# USB3A_CONN.net
KiCad netlist of a schematic drawn in Altium Designer
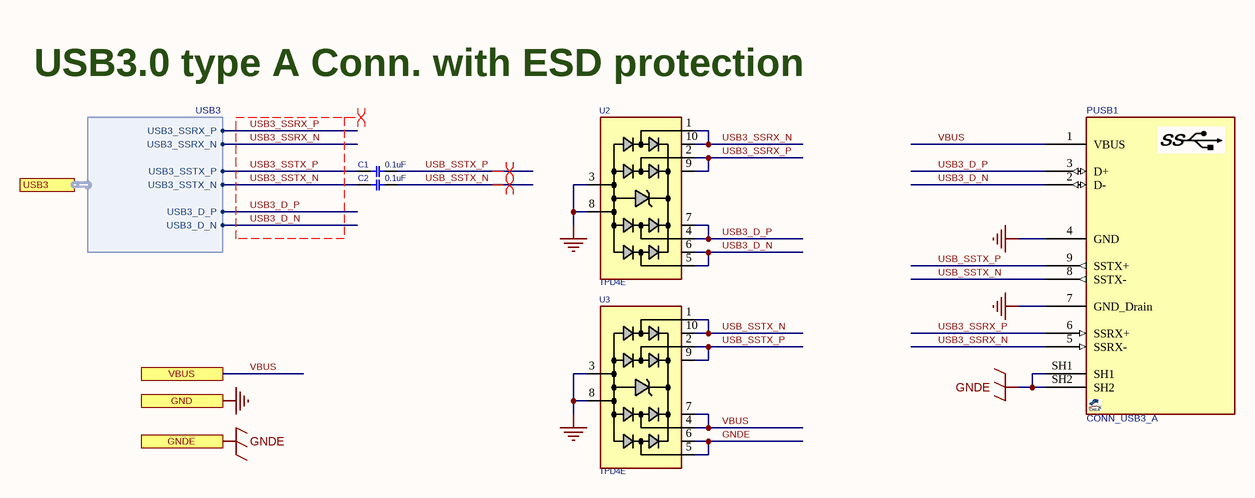
[diagram p0: USB3A_CONN.SchDoc]

(export (version "E")
  (design (tool "Eeschema 10.0.6"))
  (components
    (comp (ref "C1")
      (value "0.1uF")
      (footprint "C0201")
      (description "CAP, MLCC")
      (fields (field (name "MANF_P#") "GRM155R61E104") (field (name "MANF") "Murata"))
      (libsource (lib "passive_smd") (part "CAP_SMD_MLCC"))
    )
    (comp (ref "C2")
      (value "0.1uF")
      (footprint "C0201")
      (description "CAP, MLCC")
      (fields (field (name "MANF_P#") "GRM155R61E104") (field (name "MANF") "Murata"))
      (libsource (lib "passive_smd") (part "CAP_SMD_MLCC"))
    )
    (comp (ref "PUSB1")
      (value "CONN_USB3_A")
      (footprint "USB3_A_RA")
      (description "CONN, USB3, A type, R/A, THD")
      (fields (field (name "MANF_P#") "USB1075") (field (name "MANF") "GCT"))
      (libsource (lib "conn_usb") (part "CONN_USB3_A_USB1075"))
    )
    (comp (ref "U2")
      (value "TPD4E")
      (footprint "SON50_10_2510")
      (description "TVS, ESD PROTECT, 4CH,")
      (fields (field (name "MANF_P#") "TPD4E05U06DQA") (field (name "MANF") "Texas Instruments"))
      (libsource (lib "protect_tvs_esd_fuse") (part "TVS_X4_TPD4E05U06"))
    )
    (comp (ref "U3")
      (value "TPD4E")
      (footprint "SON50_10_2510")
      (description "TVS, ESD PROTECT, 4CH,")
      (fields (field (name "MANF_P#") "TPD4E05U06DQA") (field (name "MANF") "Texas Instruments"))
      (libsource (lib "protect_tvs_esd_fuse") (part "TVS_X4_TPD4E05U06"))
    )
  )
  (nets
    (net (code "2") (name "/USB3_D_N") (class "Default")
      (node (ref "PUSB1") (pin "2") (pinfunction "D-_2") (pintype "bidirectional"))
      (node (ref "U2") (pin "5") (pinfunction "5_5") (pintype "passive"))
      (node (ref "U2") (pin "6") (pinfunction "6_6") (pintype "passive"))
    )
    (net (code "3") (name "/USB3_D_P") (class "Default")
      (node (ref "PUSB1") (pin "3") (pinfunction "D+_3") (pintype "bidirectional"))
      (node (ref "U2") (pin "4") (pinfunction "4_4") (pintype "passive"))
      (node (ref "U2") (pin "7") (pinfunction "7_7") (pintype "passive"))
    )
    (net (code "4") (name "/USB3_SSRX_N") (class "Default")
      (node (ref "PUSB1") (pin "5") (pinfunction "SSRX-_5") (pintype "input"))
      (node (ref "U2") (pin "1") (pinfunction "1_1") (pintype "passive"))
      (node (ref "U2") (pin "10") (pinfunction "10_10") (pintype "passive"))
    )
    (net (code "5") (name "/USB3_SSRX_P") (class "Default")
      (node (ref "PUSB1") (pin "6") (pinfunction "SSRX+_6") (pintype "input"))
      (node (ref "U2") (pin "2") (pinfunction "2_2") (pintype "passive"))
      (node (ref "U2") (pin "9") (pinfunction "9_9") (pintype "passive"))
    )
    (net (code "6") (name "/USB3_SSTX_N") (class "Default")
      (node (ref "C2") (pin "1") (pinfunction "1_1") (pintype "passive"))
    )
    (net (code "7") (name "/USB3_SSTX_P") (class "Default")
      (node (ref "C1") (pin "1") (pinfunction "1_1") (pintype "passive"))
    )
    (net (code "8") (name "/USB_SSTX_N") (class "Default")
      (node (ref "C2") (pin "2") (pinfunction "2_2") (pintype "passive"))
      (node (ref "PUSB1") (pin "8") (pinfunction "SSTX-_8") (pintype "output"))
      (node (ref "U3") (pin "1") (pinfunction "1_1") (pintype "passive"))
      (node (ref "U3") (pin "10") (pinfunction "10_10") (pintype "passive"))
    )
    (net (code "9") (name "/USB_SSTX_P") (class "Default")
      (node (ref "C1") (pin "2") (pinfunction "2_2") (pintype "passive"))
      (node (ref "PUSB1") (pin "9") (pinfunction "SSTX+_9") (pintype "output"))
      (node (ref "U3") (pin "2") (pinfunction "2_2") (pintype "passive"))
      (node (ref "U3") (pin "9") (pinfunction "9_9") (pintype "passive"))
    )
    (net (code "10") (name "/VBUS") (class "Default")
      (node (ref "PUSB1") (pin "1") (pinfunction "VBUS_1") (pintype "power_in"))
      (node (ref "U3") (pin "4") (pinfunction "4_4") (pintype "passive"))
      (node (ref "U3") (pin "7") (pinfunction "7_7") (pintype "passive"))
    )
    (net (code "12") (name "GND") (class "Default")
      (node (ref "PUSB1") (pin "4") (pinfunction "GND_4") (pintype "power_in"))
      (node (ref "PUSB1") (pin "7") (pinfunction "GND_Drain_7") (pintype "power_in"))
      (node (ref "U2") (pin "3") (pinfunction "3_3") (pintype "passive"))
      (node (ref "U2") (pin "8") (pinfunction "8_8") (pintype "passive"))
      (node (ref "U3") (pin "3") (pinfunction "3_3") (pintype "passive"))
      (node (ref "U3") (pin "8") (pinfunction "8_8") (pintype "passive"))
    )
    (net (code "13") (name "GNDE") (class "Default")
      (node (ref "PUSB1") (pin "SH1") (pinfunction "SH1_SH1") (pintype "passive"))
      (node (ref "PUSB1") (pin "SH2") (pinfunction "SH2_SH2") (pintype "passive"))
      (node (ref "U3") (pin "5") (pinfunction "5_5") (pintype "passive"))
      (node (ref "U3") (pin "6") (pinfunction "6_6") (pintype "passive"))
    )
  )
)
